# Proto_Shield.net
KiCad netlist of a schematic drawn in EAGLE
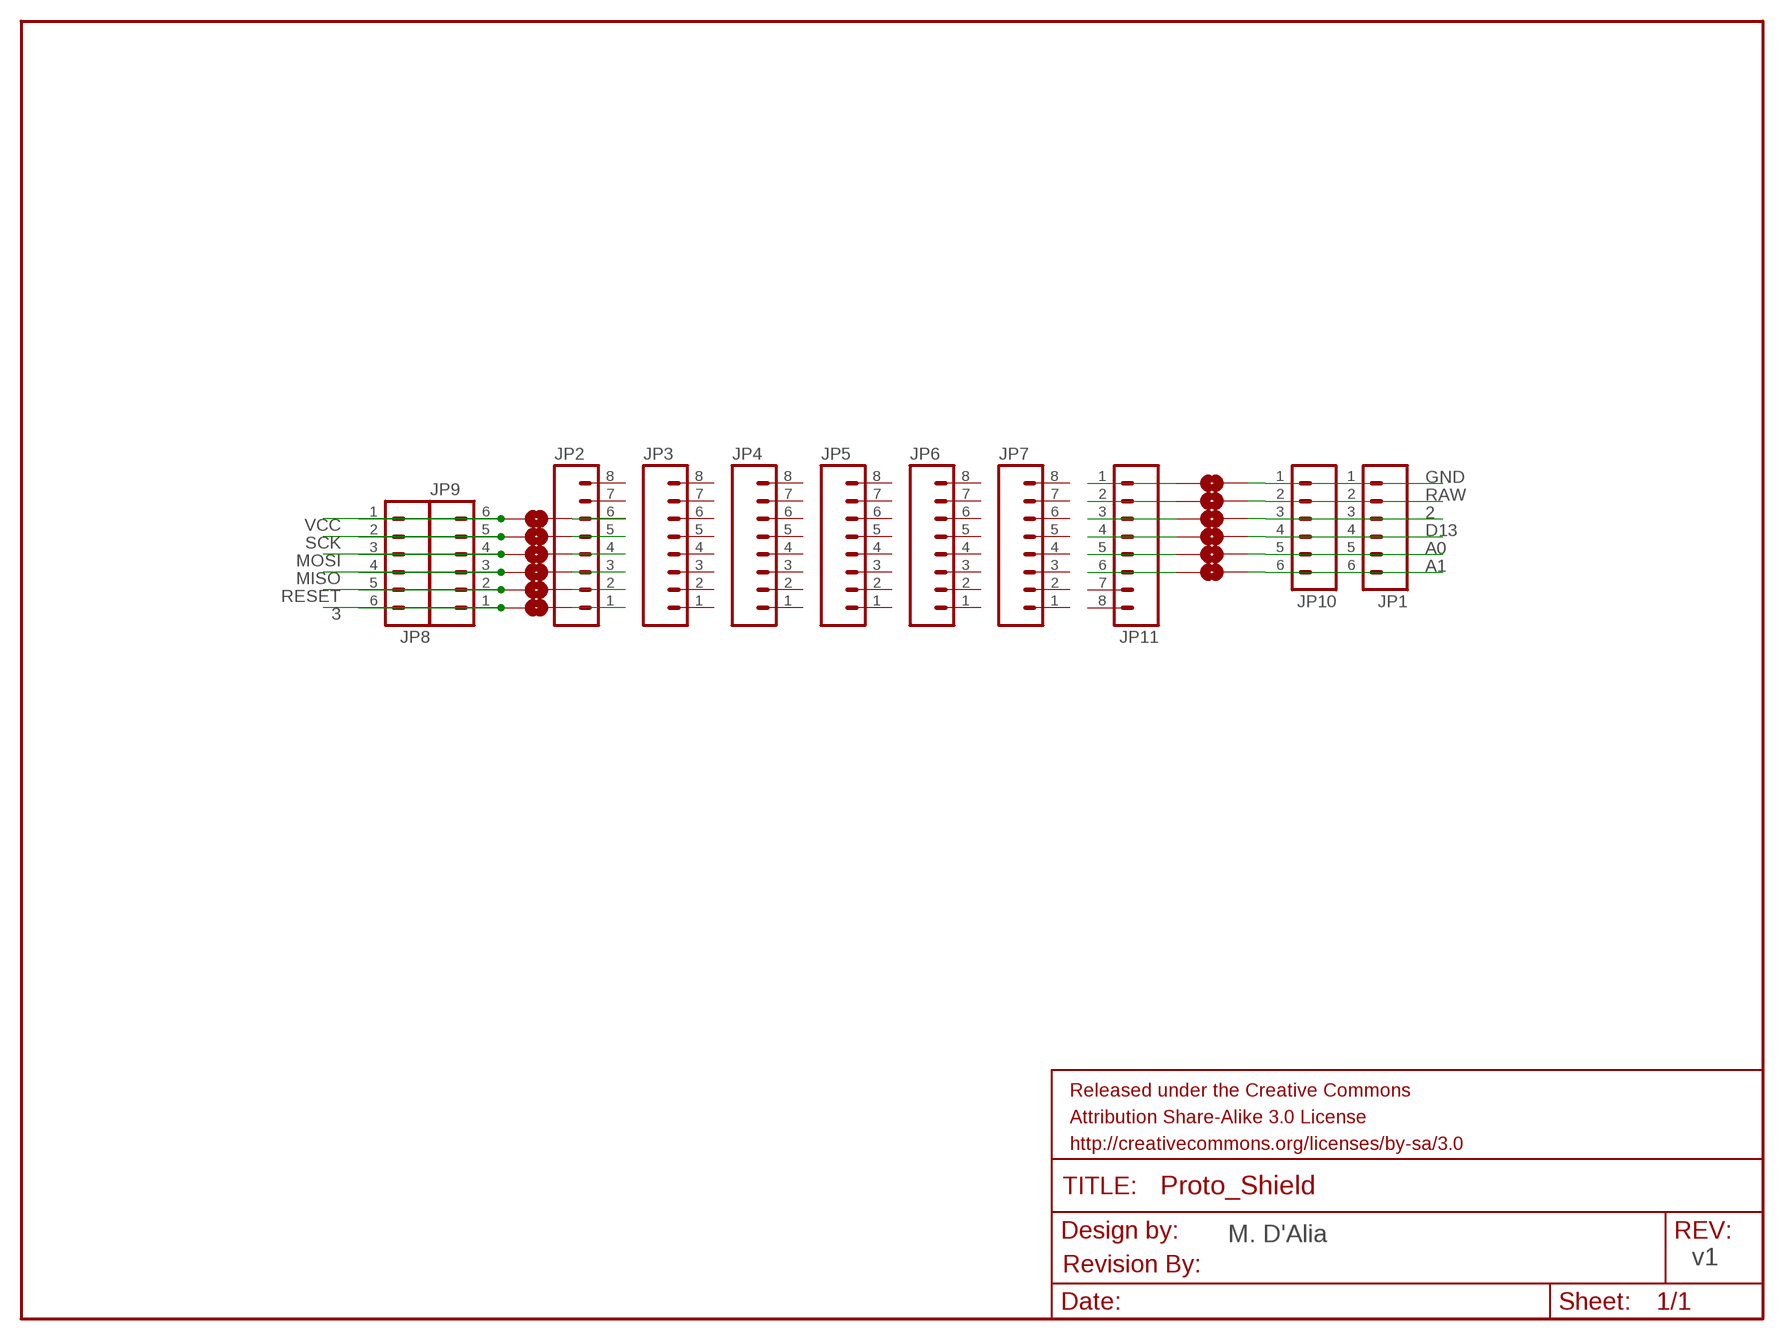
[diagram p0: schematic, sheet 1]

(export (version "E")
  (design (tool "Eeschema 10.0.6"))
  (components
    (comp (ref "FRAME1")
      (value "FRAME-LETTER")
      (footprint "eagle-import:CREATIVE_COMMONS")
      (libsource (lib "eagle-import") (part "FRAME-LETTER"))
    )
    (comp (ref "JP1")
      (value "M06SMD-STRAIGHT")
      (footprint "eagle-import:1X06_SMD_STRAIGHT")
      (libsource (lib "eagle-import") (part "M06SMD-STRAIGHT"))
    )
    (comp (ref "JP2")
      (value "M08NO_SILK")
      (footprint "eagle-import:1X08_NO_SILK")
      (libsource (lib "eagle-import") (part "M08NO_SILK"))
    )
    (comp (ref "JP3")
      (value "M08NO_SILK")
      (footprint "eagle-import:1X08_NO_SILK")
      (libsource (lib "eagle-import") (part "M08NO_SILK"))
    )
    (comp (ref "JP4")
      (value "M08NO_SILK")
      (footprint "eagle-import:1X08_NO_SILK")
      (libsource (lib "eagle-import") (part "M08NO_SILK"))
    )
    (comp (ref "JP5")
      (value "M08NO_SILK")
      (footprint "eagle-import:1X08_NO_SILK")
      (libsource (lib "eagle-import") (part "M08NO_SILK"))
    )
    (comp (ref "JP6")
      (value "M08NO_SILK")
      (footprint "eagle-import:1X08_NO_SILK")
      (libsource (lib "eagle-import") (part "M08NO_SILK"))
    )
    (comp (ref "JP7")
      (value "M08NO_SILK")
      (footprint "eagle-import:1X08_NO_SILK")
      (libsource (lib "eagle-import") (part "M08NO_SILK"))
    )
    (comp (ref "JP8")
      (value "M06SMD-STRAIGHT-ALT-NOSILK")
      (footprint "eagle-import:1X06_SMD_STRAIGHT_ALT_NOSILK")
      (libsource (lib "eagle-import") (part "M06SMD-STRAIGHT-ALT-NOSILK"))
    )
    (comp (ref "JP9")
      (value "M06LOCK_LONGPADS")
      (footprint "eagle-import:1X06_LOCK_LONGPADS")
      (libsource (lib "eagle-import") (part "M06LOCK_LONGPADS"))
    )
    (comp (ref "JP10")
      (value "M06LOCK_LONGPADS")
      (footprint "eagle-import:1X06_LOCK_LONGPADS")
      (libsource (lib "eagle-import") (part "M06LOCK_LONGPADS"))
    )
    (comp (ref "JP11")
      (value "M08NO_SILK")
      (footprint "eagle-import:1X08_NO_SILK")
      (libsource (lib "eagle-import") (part "M08NO_SILK"))
    )
    (comp (ref "SJ1")
      (value "SOLDERJUMPERTRACE")
      (footprint "eagle-import:SJ_2S-TRACE")
      (libsource (lib "eagle-import") (part "SOLDERJUMPERTRACE"))
    )
    (comp (ref "SJ2")
      (value "SOLDERJUMPERTRACE")
      (footprint "eagle-import:SJ_2S-TRACE")
      (libsource (lib "eagle-import") (part "SOLDERJUMPERTRACE"))
    )
    (comp (ref "SJ3")
      (value "SOLDERJUMPERTRACE")
      (footprint "eagle-import:SJ_2S-TRACE")
      (libsource (lib "eagle-import") (part "SOLDERJUMPERTRACE"))
    )
    (comp (ref "SJ4")
      (value "SOLDERJUMPERTRACE")
      (footprint "eagle-import:SJ_2S-TRACE")
      (libsource (lib "eagle-import") (part "SOLDERJUMPERTRACE"))
    )
    (comp (ref "SJ5")
      (value "SOLDERJUMPERTRACE")
      (footprint "eagle-import:SJ_2S-TRACE")
      (libsource (lib "eagle-import") (part "SOLDERJUMPERTRACE"))
    )
    (comp (ref "SJ6")
      (value "SOLDERJUMPERTRACE")
      (footprint "eagle-import:SJ_2S-TRACE")
      (libsource (lib "eagle-import") (part "SOLDERJUMPERTRACE"))
    )
    (comp (ref "SJ7")
      (value "SOLDERJUMPERTRACE")
      (footprint "eagle-import:SJ_2S-TRACE")
      (libsource (lib "eagle-import") (part "SOLDERJUMPERTRACE"))
    )
    (comp (ref "SJ8")
      (value "SOLDERJUMPERTRACE")
      (footprint "eagle-import:SJ_2S-TRACE")
      (libsource (lib "eagle-import") (part "SOLDERJUMPERTRACE"))
    )
    (comp (ref "SJ9")
      (value "SOLDERJUMPERTRACE")
      (footprint "eagle-import:SJ_2S-TRACE")
      (libsource (lib "eagle-import") (part "SOLDERJUMPERTRACE"))
    )
    (comp (ref "SJ10")
      (value "SOLDERJUMPERTRACE")
      (footprint "eagle-import:SJ_2S-TRACE")
      (libsource (lib "eagle-import") (part "SOLDERJUMPERTRACE"))
    )
    (comp (ref "SJ11")
      (value "SOLDERJUMPERTRACE")
      (footprint "eagle-import:SJ_2S-TRACE")
      (libsource (lib "eagle-import") (part "SOLDERJUMPERTRACE"))
    )
    (comp (ref "SJ12")
      (value "SOLDERJUMPERTRACE")
      (footprint "eagle-import:SJ_2S-TRACE")
      (libsource (lib "eagle-import") (part "SOLDERJUMPERTRACE"))
    )
    (comp (ref "U$5")
      (value "REVISION")
      (footprint "eagle-import:REVISION")
      (libsource (lib "eagle-import") (part "REVISION"))
    )
  )
  (nets
    (net (code "1") (name "/2") (class "Default")
      (node (ref "JP1") (pin "3") (pinfunction "3_3") (pintype "passive"))
      (node (ref "JP10") (pin "3") (pinfunction "3_3") (pintype "passive"))
      (node (ref "SJ4") (pin "1") (pinfunction "1_1") (pintype "passive"))
    )
    (net (code "2") (name "/3") (class "Default")
      (node (ref "JP8") (pin "6") (pinfunction "6_6") (pintype "passive"))
      (node (ref "JP9") (pin "1") (pinfunction "1_1") (pintype "passive"))
      (node (ref "SJ12") (pin "2") (pinfunction "2_2") (pintype "passive"))
    )
    (net (code "3") (name "/A0") (class "Default")
      (node (ref "JP1") (pin "5") (pinfunction "5_5") (pintype "passive"))
      (node (ref "JP10") (pin "5") (pinfunction "5_5") (pintype "passive"))
      (node (ref "SJ2") (pin "1") (pinfunction "1_1") (pintype "passive"))
    )
    (net (code "4") (name "/A1") (class "Default")
      (node (ref "JP1") (pin "6") (pinfunction "6_6") (pintype "passive"))
      (node (ref "JP10") (pin "6") (pinfunction "6_6") (pintype "passive"))
      (node (ref "SJ1") (pin "1") (pinfunction "1_1") (pintype "passive"))
    )
    (net (code "5") (name "/D13") (class "Default")
      (node (ref "JP1") (pin "4") (pinfunction "4_4") (pintype "passive"))
      (node (ref "JP10") (pin "4") (pinfunction "4_4") (pintype "passive"))
      (node (ref "SJ3") (pin "1") (pinfunction "1_1") (pintype "passive"))
    )
    (net (code "6") (name "/GND") (class "Default")
      (node (ref "JP1") (pin "1") (pinfunction "1_1") (pintype "passive"))
      (node (ref "JP10") (pin "1") (pinfunction "1_1") (pintype "passive"))
      (node (ref "SJ6") (pin "1") (pinfunction "1_1") (pintype "passive"))
    )
    (net (code "7") (name "/MISO") (class "Default")
      (node (ref "JP8") (pin "4") (pinfunction "4_4") (pintype "passive"))
      (node (ref "JP9") (pin "3") (pinfunction "3_3") (pintype "passive"))
      (node (ref "SJ10") (pin "2") (pinfunction "2_2") (pintype "passive"))
    )
    (net (code "8") (name "/MOSI") (class "Default")
      (node (ref "JP8") (pin "3") (pinfunction "3_3") (pintype "passive"))
      (node (ref "JP9") (pin "4") (pinfunction "4_4") (pintype "passive"))
      (node (ref "SJ9") (pin "2") (pinfunction "2_2") (pintype "passive"))
    )
    (net (code "9") (name "/RAW") (class "Default")
      (node (ref "JP1") (pin "2") (pinfunction "2_2") (pintype "passive"))
      (node (ref "JP10") (pin "2") (pinfunction "2_2") (pintype "passive"))
      (node (ref "SJ5") (pin "1") (pinfunction "1_1") (pintype "passive"))
    )
    (net (code "10") (name "/RESET") (class "Default")
      (node (ref "JP8") (pin "5") (pinfunction "5_5") (pintype "passive"))
      (node (ref "JP9") (pin "2") (pinfunction "2_2") (pintype "passive"))
      (node (ref "SJ11") (pin "2") (pinfunction "2_2") (pintype "passive"))
    )
    (net (code "11") (name "/SCK") (class "Default")
      (node (ref "JP8") (pin "2") (pinfunction "2_2") (pintype "passive"))
      (node (ref "JP9") (pin "5") (pinfunction "5_5") (pintype "passive"))
      (node (ref "SJ8") (pin "2") (pinfunction "2_2") (pintype "passive"))
    )
    (net (code "12") (name "/VCC") (class "Default")
      (node (ref "JP8") (pin "1") (pinfunction "1_1") (pintype "passive"))
      (node (ref "JP9") (pin "6") (pinfunction "6_6") (pintype "passive"))
      (node (ref "SJ7") (pin "2") (pinfunction "2_2") (pintype "passive"))
    )
    (net (code "13") (name "Net-(JP2-Pad1)") (class "Default")
      (node (ref "JP2") (pin "1") (pinfunction "1_1") (pintype "passive"))
      (node (ref "SJ12") (pin "1") (pinfunction "1_1") (pintype "passive"))
    )
    (net (code "14") (name "Net-(JP2-Pad2)") (class "Default")
      (node (ref "JP2") (pin "2") (pinfunction "2_2") (pintype "passive"))
      (node (ref "SJ11") (pin "1") (pinfunction "1_1") (pintype "passive"))
    )
    (net (code "15") (name "Net-(JP2-Pad3)") (class "Default")
      (node (ref "JP2") (pin "3") (pinfunction "3_3") (pintype "passive"))
      (node (ref "SJ10") (pin "1") (pinfunction "1_1") (pintype "passive"))
    )
    (net (code "16") (name "Net-(JP2-Pad4)") (class "Default")
      (node (ref "JP2") (pin "4") (pinfunction "4_4") (pintype "passive"))
      (node (ref "SJ9") (pin "1") (pinfunction "1_1") (pintype "passive"))
    )
    (net (code "17") (name "Net-(JP2-Pad5)") (class "Default")
      (node (ref "JP2") (pin "5") (pinfunction "5_5") (pintype "passive"))
      (node (ref "SJ8") (pin "1") (pinfunction "1_1") (pintype "passive"))
    )
    (net (code "18") (name "Net-(JP2-Pad6)") (class "Default")
      (node (ref "JP2") (pin "6") (pinfunction "6_6") (pintype "passive"))
      (node (ref "SJ7") (pin "1") (pinfunction "1_1") (pintype "passive"))
    )
    (net (code "19") (name "Net-(JP11-Pad1)") (class "Default")
      (node (ref "JP11") (pin "1") (pinfunction "1_1") (pintype "passive"))
      (node (ref "SJ6") (pin "2") (pinfunction "2_2") (pintype "passive"))
    )
    (net (code "20") (name "Net-(JP11-Pad2)") (class "Default")
      (node (ref "JP11") (pin "2") (pinfunction "2_2") (pintype "passive"))
      (node (ref "SJ5") (pin "2") (pinfunction "2_2") (pintype "passive"))
    )
    (net (code "21") (name "Net-(JP11-Pad3)") (class "Default")
      (node (ref "JP11") (pin "3") (pinfunction "3_3") (pintype "passive"))
      (node (ref "SJ4") (pin "2") (pinfunction "2_2") (pintype "passive"))
    )
    (net (code "22") (name "Net-(JP11-Pad4)") (class "Default")
      (node (ref "JP11") (pin "4") (pinfunction "4_4") (pintype "passive"))
      (node (ref "SJ3") (pin "2") (pinfunction "2_2") (pintype "passive"))
    )
    (net (code "23") (name "Net-(JP11-Pad5)") (class "Default")
      (node (ref "JP11") (pin "5") (pinfunction "5_5") (pintype "passive"))
      (node (ref "SJ2") (pin "2") (pinfunction "2_2") (pintype "passive"))
    )
    (net (code "24") (name "Net-(JP11-Pad6)") (class "Default")
      (node (ref "JP11") (pin "6") (pinfunction "6_6") (pintype "passive"))
      (node (ref "SJ1") (pin "2") (pinfunction "2_2") (pintype "passive"))
    )
    (net (code "25") (name "unconnected-(JP2-Pad7)") (class "Default")
      (node (ref "JP2") (pin "7") (pinfunction "7_7") (pintype "passive"))
    )
    (net (code "26") (name "unconnected-(JP2-Pad8)") (class "Default")
      (node (ref "JP2") (pin "8") (pinfunction "8_8") (pintype "passive"))
    )
    (net (code "27") (name "unconnected-(JP3-Pad1)") (class "Default")
      (node (ref "JP3") (pin "1") (pinfunction "1_1") (pintype "passive"))
    )
    (net (code "28") (name "unconnected-(JP3-Pad2)") (class "Default")
      (node (ref "JP3") (pin "2") (pinfunction "2_2") (pintype "passive"))
    )
    (net (code "29") (name "unconnected-(JP3-Pad3)") (class "Default")
      (node (ref "JP3") (pin "3") (pinfunction "3_3") (pintype "passive"))
    )
    (net (code "30") (name "unconnected-(JP3-Pad4)") (class "Default")
      (node (ref "JP3") (pin "4") (pinfunction "4_4") (pintype "passive"))
    )
    (net (code "31") (name "unconnected-(JP3-Pad5)") (class "Default")
      (node (ref "JP3") (pin "5") (pinfunction "5_5") (pintype "passive"))
    )
    (net (code "32") (name "unconnected-(JP3-Pad6)") (class "Default")
      (node (ref "JP3") (pin "6") (pinfunction "6_6") (pintype "passive"))
    )
    (net (code "33") (name "unconnected-(JP3-Pad7)") (class "Default")
      (node (ref "JP3") (pin "7") (pinfunction "7_7") (pintype "passive"))
    )
    (net (code "34") (name "unconnected-(JP3-Pad8)") (class "Default")
      (node (ref "JP3") (pin "8") (pinfunction "8_8") (pintype "passive"))
    )
    (net (code "35") (name "unconnected-(JP4-Pad1)") (class "Default")
      (node (ref "JP4") (pin "1") (pinfunction "1_1") (pintype "passive"))
    )
    (net (code "36") (name "unconnected-(JP4-Pad2)") (class "Default")
      (node (ref "JP4") (pin "2") (pinfunction "2_2") (pintype "passive"))
    )
    (net (code "37") (name "unconnected-(JP4-Pad3)") (class "Default")
      (node (ref "JP4") (pin "3") (pinfunction "3_3") (pintype "passive"))
    )
    (net (code "38") (name "unconnected-(JP4-Pad4)") (class "Default")
      (node (ref "JP4") (pin "4") (pinfunction "4_4") (pintype "passive"))
    )
    (net (code "39") (name "unconnected-(JP4-Pad5)") (class "Default")
      (node (ref "JP4") (pin "5") (pinfunction "5_5") (pintype "passive"))
    )
    (net (code "40") (name "unconnected-(JP4-Pad6)") (class "Default")
      (node (ref "JP4") (pin "6") (pinfunction "6_6") (pintype "passive"))
    )
    (net (code "41") (name "unconnected-(JP4-Pad7)") (class "Default")
      (node (ref "JP4") (pin "7") (pinfunction "7_7") (pintype "passive"))
    )
    (net (code "42") (name "unconnected-(JP4-Pad8)") (class "Default")
      (node (ref "JP4") (pin "8") (pinfunction "8_8") (pintype "passive"))
    )
    (net (code "43") (name "unconnected-(JP5-Pad1)") (class "Default")
      (node (ref "JP5") (pin "1") (pinfunction "1_1") (pintype "passive"))
    )
    (net (code "44") (name "unconnected-(JP5-Pad2)") (class "Default")
      (node (ref "JP5") (pin "2") (pinfunction "2_2") (pintype "passive"))
    )
    (net (code "45") (name "unconnected-(JP5-Pad3)") (class "Default")
      (node (ref "JP5") (pin "3") (pinfunction "3_3") (pintype "passive"))
    )
    (net (code "46") (name "unconnected-(JP5-Pad4)") (class "Default")
      (node (ref "JP5") (pin "4") (pinfunction "4_4") (pintype "passive"))
    )
    (net (code "47") (name "unconnected-(JP5-Pad5)") (class "Default")
      (node (ref "JP5") (pin "5") (pinfunction "5_5") (pintype "passive"))
    )
    (net (code "48") (name "unconnected-(JP5-Pad6)") (class "Default")
      (node (ref "JP5") (pin "6") (pinfunction "6_6") (pintype "passive"))
    )
    (net (code "49") (name "unconnected-(JP5-Pad7)") (class "Default")
      (node (ref "JP5") (pin "7") (pinfunction "7_7") (pintype "passive"))
    )
    (net (code "50") (name "unconnected-(JP5-Pad8)") (class "Default")
      (node (ref "JP5") (pin "8") (pinfunction "8_8") (pintype "passive"))
    )
    (net (code "51") (name "unconnected-(JP6-Pad1)") (class "Default")
      (node (ref "JP6") (pin "1") (pinfunction "1_1") (pintype "passive"))
    )
    (net (code "52") (name "unconnected-(JP6-Pad2)") (class "Default")
      (node (ref "JP6") (pin "2") (pinfunction "2_2") (pintype "passive"))
    )
    (net (code "53") (name "unconnected-(JP6-Pad3)") (class "Default")
      (node (ref "JP6") (pin "3") (pinfunction "3_3") (pintype "passive"))
    )
    (net (code "54") (name "unconnected-(JP6-Pad4)") (class "Default")
      (node (ref "JP6") (pin "4") (pinfunction "4_4") (pintype "passive"))
    )
    (net (code "55") (name "unconnected-(JP6-Pad5)") (class "Default")
      (node (ref "JP6") (pin "5") (pinfunction "5_5") (pintype "passive"))
    )
    (net (code "56") (name "unconnected-(JP6-Pad6)") (class "Default")
      (node (ref "JP6") (pin "6") (pinfunction "6_6") (pintype "passive"))
    )
    (net (code "57") (name "unconnected-(JP6-Pad7)") (class "Default")
      (node (ref "JP6") (pin "7") (pinfunction "7_7") (pintype "passive"))
    )
    (net (code "58") (name "unconnected-(JP6-Pad8)") (class "Default")
      (node (ref "JP6") (pin "8") (pinfunction "8_8") (pintype "passive"))
    )
    (net (code "59") (name "unconnected-(JP7-Pad1)") (class "Default")
      (node (ref "JP7") (pin "1") (pinfunction "1_1") (pintype "passive"))
    )
    (net (code "60") (name "unconnected-(JP7-Pad2)") (class "Default")
      (node (ref "JP7") (pin "2") (pinfunction "2_2") (pintype "passive"))
    )
    (net (code "61") (name "unconnected-(JP7-Pad3)") (class "Default")
      (node (ref "JP7") (pin "3") (pinfunction "3_3") (pintype "passive"))
    )
    (net (code "62") (name "unconnected-(JP7-Pad4)") (class "Default")
      (node (ref "JP7") (pin "4") (pinfunction "4_4") (pintype "passive"))
    )
    (net (code "63") (name "unconnected-(JP7-Pad5)") (class "Default")
      (node (ref "JP7") (pin "5") (pinfunction "5_5") (pintype "passive"))
    )
    (net (code "64") (name "unconnected-(JP7-Pad6)") (class "Default")
      (node (ref "JP7") (pin "6") (pinfunction "6_6") (pintype "passive"))
    )
    (net (code "65") (name "unconnected-(JP7-Pad7)") (class "Default")
      (node (ref "JP7") (pin "7") (pinfunction "7_7") (pintype "passive"))
    )
    (net (code "66") (name "unconnected-(JP7-Pad8)") (class "Default")
      (node (ref "JP7") (pin "8") (pinfunction "8_8") (pintype "passive"))
    )
    (net (code "67") (name "unconnected-(JP11-Pad7)") (class "Default")
      (node (ref "JP11") (pin "7") (pinfunction "7_7") (pintype "passive"))
    )
    (net (code "68") (name "unconnected-(JP11-Pad8)") (class "Default")
      (node (ref "JP11") (pin "8") (pinfunction "8_8") (pintype "passive"))
    )
  )
)
